# ArduOSD_Simple2222.net
KiCad netlist of a schematic drawn in EAGLE
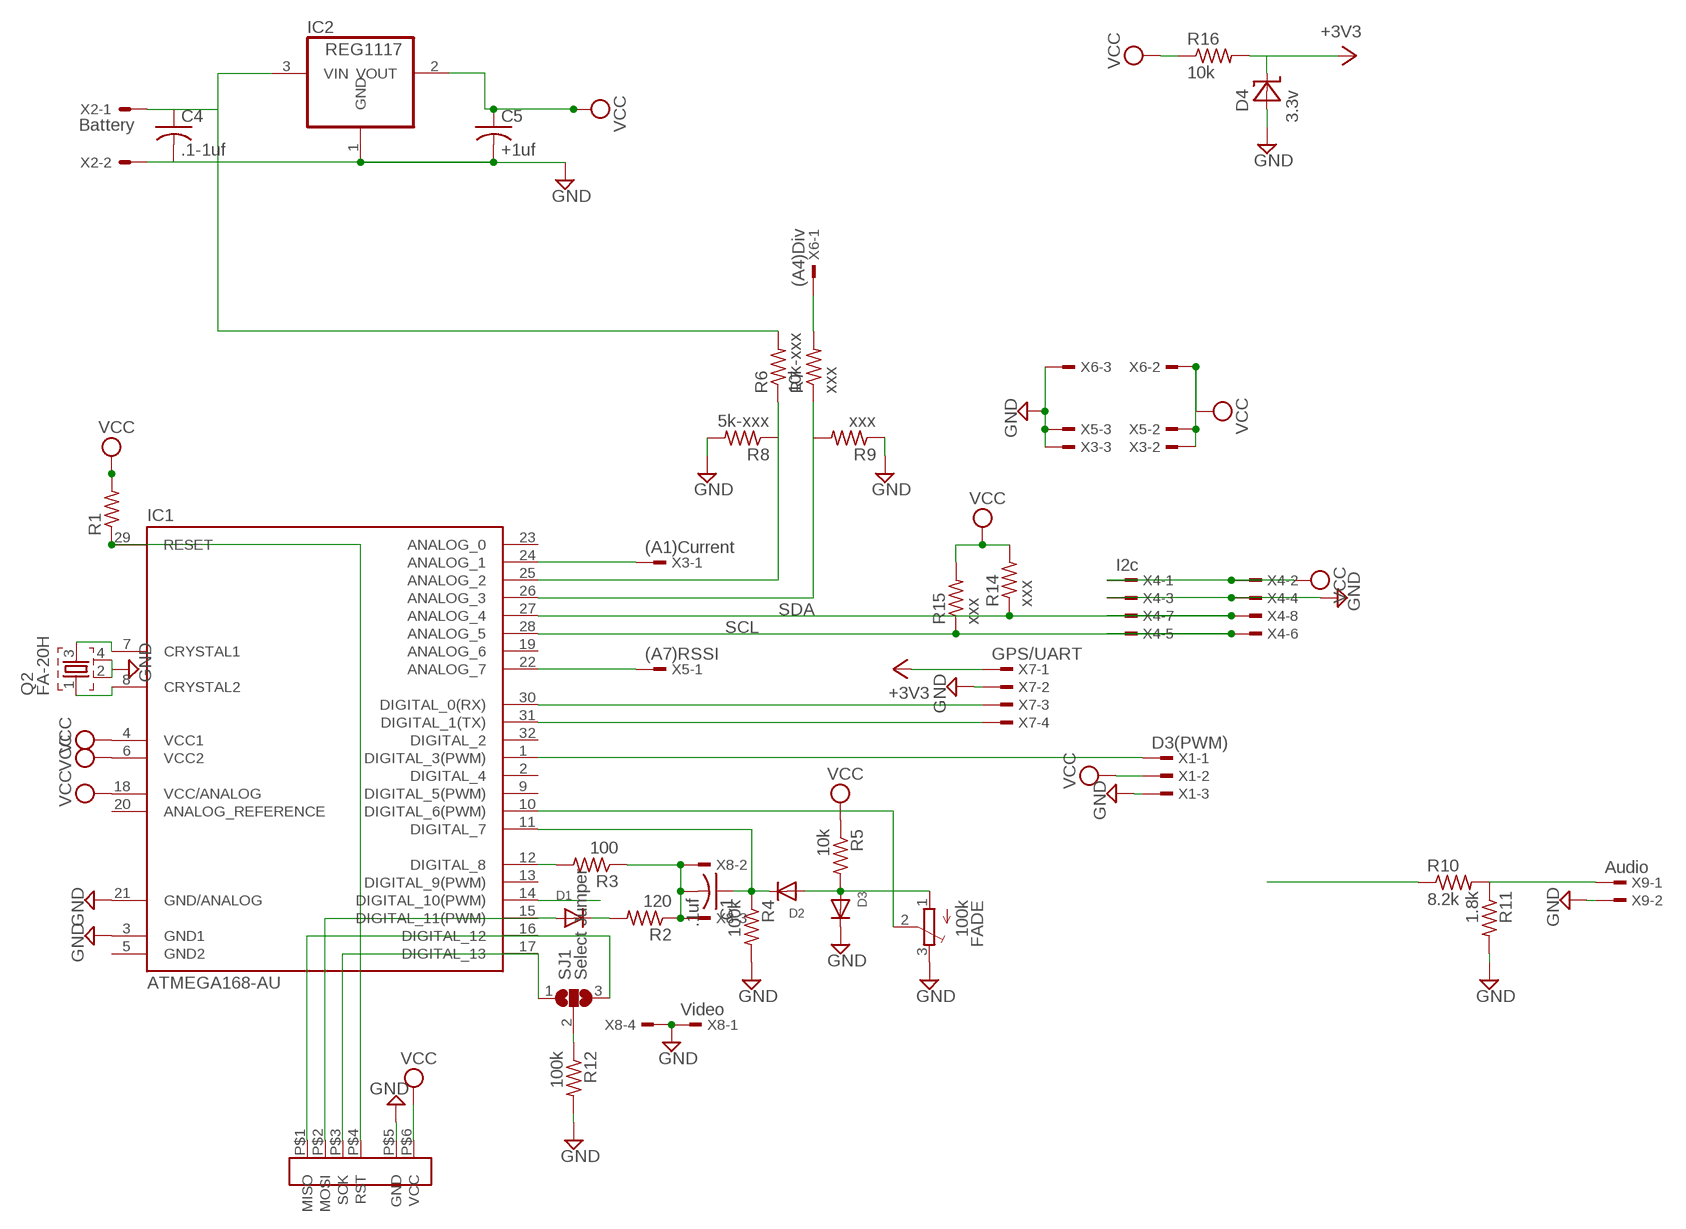
[diagram p0: schematic, sheet 1]

(export (version "E")
  (design (tool "Eeschema 10.0.6"))
  (components
    (comp (ref "C1")
      (value ".1uf")
      (footprint "eagle-import:C0805K")
      (libsource (lib "eagle-import") (part "C-USC0805K"))
    )
    (comp (ref "C4")
      (value ".1-1uf")
      (footprint "eagle-import:C0805K")
      (libsource (lib "eagle-import") (part "C-USC0805K"))
    )
    (comp (ref "C5")
      (value "+1uf")
      (footprint "eagle-import:C0805K")
      (libsource (lib "eagle-import") (part "C-USC0805K"))
    )
    (comp (ref "D1")
      (value "DIODESOT23_WAVE")
      (footprint "eagle-import:SOT23-W")
      (libsource (lib "eagle-import") (part "DIODESOT23_WAVE"))
    )
    (comp (ref "D2")
      (value "DIODESOT23_WAVE")
      (footprint "eagle-import:SOT23-W")
      (libsource (lib "eagle-import") (part "DIODESOT23_WAVE"))
    )
    (comp (ref "D3")
      (value "DIODESOT23_WAVE")
      (footprint "eagle-import:SOT23-W")
      (libsource (lib "eagle-import") (part "DIODESOT23_WAVE"))
    )
    (comp (ref "D4")
      (value "3.3v")
      (footprint "eagle-import:SOD-123")
      (libsource (lib "eagle-import") (part "ZENER_SOD123"))
    )
    (comp (ref "FADE")
      (value "100k")
      (footprint "eagle-import:TC33X")
      (libsource (lib "eagle-import") (part "TRIMPOTTC33X"))
    )
    (comp (ref "IC1")
      (value "ATMEGA168-AU")
      (footprint "eagle-import:TQFP32-08")
      (libsource (lib "eagle-import") (part "ATMEGA168-AU"))
    )
    (comp (ref "IC2")
      (value "REG1117")
      (footprint "eagle-import:SOT223")
      (libsource (lib "eagle-import") (part "REG1117"))
    )
    (comp (ref "Q2")
      (value "FA-20H")
      (footprint "eagle-import:FA-20H")
      (libsource (lib "eagle-import") (part "FA-20H"))
    )
    (comp (ref "R1")
      (value "R-US_R0805")
      (footprint "eagle-import:R0805")
      (libsource (lib "eagle-import") (part "R-US_R0805"))
    )
    (comp (ref "R2")
      (value "120")
      (footprint "eagle-import:R0805")
      (libsource (lib "eagle-import") (part "R-US_R0805"))
    )
    (comp (ref "R3")
      (value "100")
      (footprint "eagle-import:R0805")
      (libsource (lib "eagle-import") (part "R-US_R0805"))
    )
    (comp (ref "R4")
      (value "100k")
      (footprint "eagle-import:R0805")
      (libsource (lib "eagle-import") (part "R-US_R0805"))
    )
    (comp (ref "R5")
      (value "10k")
      (footprint "eagle-import:R0805")
      (libsource (lib "eagle-import") (part "R-US_R0805"))
    )
    (comp (ref "R6")
      (value "10k-xxx")
      (footprint "eagle-import:R0805")
      (libsource (lib "eagle-import") (part "R-US_R0805"))
    )
    (comp (ref "R7")
      (value "xxx")
      (footprint "eagle-import:R0805")
      (libsource (lib "eagle-import") (part "R-US_R0805"))
    )
    (comp (ref "R8")
      (value "5k-xxx")
      (footprint "eagle-import:R0805")
      (libsource (lib "eagle-import") (part "R-US_R0805"))
    )
    (comp (ref "R9")
      (value "xxx")
      (footprint "eagle-import:R0805")
      (libsource (lib "eagle-import") (part "R-US_R0805"))
    )
    (comp (ref "R10")
      (value "8.2k")
      (footprint "eagle-import:R0805")
      (libsource (lib "eagle-import") (part "R-US_R0805"))
    )
    (comp (ref "R11")
      (value "1.8k")
      (footprint "eagle-import:R0805")
      (libsource (lib "eagle-import") (part "R-US_R0805"))
    )
    (comp (ref "R12")
      (value "100k")
      (footprint "eagle-import:R0805")
      (libsource (lib "eagle-import") (part "R-US_R0805"))
    )
    (comp (ref "R14")
      (value "xxx")
      (footprint "eagle-import:R0805")
      (libsource (lib "eagle-import") (part "R-US_R0805"))
    )
    (comp (ref "R15")
      (value "xxx")
      (footprint "eagle-import:R0805")
      (libsource (lib "eagle-import") (part "R-US_R0805"))
    )
    (comp (ref "R16")
      (value "10k")
      (footprint "eagle-import:R0805")
      (libsource (lib "eagle-import") (part "R-US_R0805"))
    )
    (comp (ref "SJ1")
      (value "Select Jumper")
      (footprint "eagle-import:SJ_2")
      (libsource (lib "eagle-import") (part "SJ2W"))
    )
    (comp (ref "U$1")
      (value "LIN_ISP")
      (footprint "eagle-import:LINEAR_ISP")
      (libsource (lib "eagle-import") (part "LIN_ISP"))
    )
    (comp (ref "X1")
      (value "D3(PWM)")
      (footprint "eagle-import:TSW-103-02-S-S")
      (fields (field (name "OC_FARNELL") "unknown") (field (name "OC_NEWARK") "unknown"))
      (libsource (lib "eagle-import") (part "TSW-103-02-S-S"))
    )
    (comp (ref "X2")
      (value "Battery")
      (footprint "eagle-import:22-23-2021")
      (fields (field (name "MF") "MOLEX") (field (name "MPN") "22-23-2021"))
      (libsource (lib "eagle-import") (part "22-23-2021"))
    )
    (comp (ref "X3")
      (value "(A1)Current")
      (footprint "eagle-import:TSW-103-02-S-S")
      (libsource (lib "eagle-import") (part "TSW-103-02-S-S"))
    )
    (comp (ref "X4")
      (value "I2c")
      (footprint "eagle-import:TSW-104-02-S-D-RA")
      (libsource (lib "eagle-import") (part "TSW-104-02-S-D-RA"))
    )
    (comp (ref "X5")
      (value "(A7)RSSI")
      (footprint "eagle-import:TSW-103-02-S-S")
      (libsource (lib "eagle-import") (part "TSW-103-02-S-S"))
    )
    (comp (ref "X6")
      (value "(A4)Div")
      (footprint "eagle-import:TSW-103-02-S-S")
      (fields (field (name "OC_FARNELL") "unknown") (field (name "OC_NEWARK") "unknown"))
      (libsource (lib "eagle-import") (part "TSW-103-02-S-S"))
    )
    (comp (ref "X7")
      (value "GPS/UART")
      (footprint "eagle-import:TSW-104-02-S-S-RA")
      (libsource (lib "eagle-import") (part "TSW-104-02-S-S-RA"))
    )
    (comp (ref "X8")
      (value "Video")
      (footprint "eagle-import:TSW-104-02-S-S-RA")
      (libsource (lib "eagle-import") (part "TSW-104-02-S-S-RA"))
    )
    (comp (ref "X9")
      (value "Audio")
      (footprint "eagle-import:TSW-102-02-S-S-RA")
      (fields (field (name "OC_FARNELL") "unknown") (field (name "OC_NEWARK") "unknown"))
      (libsource (lib "eagle-import") (part "TSW-102-02-S-S-RA"))
    )
  )
  (nets
    (net (code "1") (name "+3V3") (class "Default")
      (node (ref "D4") (pin "1") (pinfunction "C_1") (pintype "passive"))
      (node (ref "R16") (pin "2") (pinfunction "2_2") (pintype "passive"))
      (node (ref "X7") (pin "1") (pinfunction "1_1") (pintype "passive"))
    )
    (net (code "2") (name "/DIGITAL_10") (class "Default")
      (node (ref "IC1") (pin "14") (pinfunction "DIGITAL_10(PWM)_14") (pintype "bidirectional"))
      (node (ref "R10") (pin "1") (pinfunction "1_1") (pintype "passive"))
    )
    (net (code "3") (name "/GND2") (class "Default")
      (node (ref "IC1") (pin "5") (pinfunction "GND2_5") (pintype "power_in"))
    )
    (net (code "4") (name "/SCL") (class "Default")
      (node (ref "IC1") (pin "28") (pinfunction "ANALOG_5_28") (pintype "bidirectional"))
      (node (ref "R15") (pin "1") (pinfunction "1_1") (pintype "passive"))
      (node (ref "X4") (pin "5") (pinfunction "1_5") (pintype "passive"))
      (node (ref "X4") (pin "6") (pinfunction "1_6") (pintype "passive"))
    )
    (net (code "5") (name "/SDA") (class "Default")
      (node (ref "IC1") (pin "27") (pinfunction "ANALOG_4_27") (pintype "bidirectional"))
      (node (ref "R14") (pin "1") (pinfunction "1_1") (pintype "passive"))
      (node (ref "X4") (pin "7") (pinfunction "1_7") (pintype "passive"))
      (node (ref "X4") (pin "8") (pinfunction "1_8") (pintype "passive"))
    )
    (net (code "6") (name "GND") (class "Default")
      (node (ref "C4") (pin "2") (pinfunction "2_2") (pintype "passive"))
      (node (ref "C5") (pin "2") (pinfunction "2_2") (pintype "passive"))
      (node (ref "D3") (pin "3") (pinfunction "C_3") (pintype "passive"))
      (node (ref "D4") (pin "2") (pinfunction "A_2") (pintype "passive"))
      (node (ref "FADE") (pin "3") (pinfunction "E_3") (pintype "passive"))
      (node (ref "IC1") (pin "21") (pinfunction "GND/ANALOG_21") (pintype "power_in"))
      (node (ref "IC1") (pin "3") (pinfunction "GND1_3") (pintype "power_in"))
      (node (ref "IC2") (pin "1") (pinfunction "GND_1") (pintype "power_in"))
      (node (ref "Q2") (pin "2") (pinfunction "2_2") (pintype "passive"))
      (node (ref "Q2") (pin "4") (pinfunction "4_4") (pintype "passive"))
      (node (ref "R11") (pin "2") (pinfunction "2_2") (pintype "passive"))
      (node (ref "R12") (pin "2") (pinfunction "2_2") (pintype "passive"))
      (node (ref "R4") (pin "2") (pinfunction "2_2") (pintype "passive"))
      (node (ref "R8") (pin "2") (pinfunction "2_2") (pintype "passive"))
      (node (ref "R9") (pin "1") (pinfunction "1_1") (pintype "passive"))
      (node (ref "U$1") (pin "P$5") (pinfunction "GND_P$5") (pintype "bidirectional"))
      (node (ref "X1") (pin "3") (pinfunction "1_3") (pintype "passive"))
      (node (ref "X2") (pin "2") (pinfunction "S_2") (pintype "passive"))
      (node (ref "X3") (pin "3") (pinfunction "1_3") (pintype "passive"))
      (node (ref "X4") (pin "3") (pinfunction "1_3") (pintype "passive"))
      (node (ref "X4") (pin "4") (pinfunction "1_4") (pintype "passive"))
      (node (ref "X5") (pin "3") (pinfunction "1_3") (pintype "passive"))
      (node (ref "X6") (pin "3") (pinfunction "1_3") (pintype "passive"))
      (node (ref "X7") (pin "2") (pinfunction "1_2") (pintype "passive"))
      (node (ref "X8") (pin "1") (pinfunction "1_1") (pintype "passive"))
      (node (ref "X8") (pin "4") (pinfunction "1_4") (pintype "passive"))
      (node (ref "X9") (pin "2") (pinfunction "1_2") (pintype "passive"))
    )
    (net (code "7") (name "Net-(D1-A)") (class "Default")
      (node (ref "D1") (pin "1") (pinfunction "A_1") (pintype "passive"))
      (node (ref "IC1") (pin "15") (pinfunction "DIGITAL_11(PWM)_15") (pintype "bidirectional"))
      (node (ref "U$1") (pin "P$2") (pinfunction "MOSI_P$2") (pintype "bidirectional"))
    )
    (net (code "8") (name "Net-(D1-C)") (class "Default")
      (node (ref "D1") (pin "3") (pinfunction "C_3") (pintype "passive"))
      (node (ref "R2") (pin "2") (pinfunction "2_2") (pintype "passive"))
    )
    (net (code "9") (name "Net-(D2-A)") (class "Default")
      (node (ref "D2") (pin "1") (pinfunction "A_1") (pintype "passive"))
      (node (ref "D3") (pin "1") (pinfunction "A_1") (pintype "passive"))
      (node (ref "FADE") (pin "1") (pinfunction "A_1") (pintype "passive"))
      (node (ref "R5") (pin "2") (pinfunction "2_2") (pintype "passive"))
    )
    (net (code "10") (name "Net-(D2-C)") (class "Default")
      (node (ref "C1") (pin "1") (pinfunction "1_1") (pintype "passive"))
      (node (ref "D2") (pin "3") (pinfunction "C_3") (pintype "passive"))
      (node (ref "IC1") (pin "11") (pinfunction "DIGITAL_7_11") (pintype "bidirectional"))
      (node (ref "R4") (pin "1") (pinfunction "1_1") (pintype "passive"))
    )
    (net (code "11") (name "Net-(FADE-S)") (class "Default")
      (node (ref "FADE") (pin "2") (pinfunction "S_2") (pintype "passive"))
      (node (ref "IC1") (pin "10") (pinfunction "DIGITAL_6(PWM)_10") (pintype "bidirectional"))
    )
    (net (code "12") (name "Net-(IC1-ANALOG_1)") (class "Default")
      (node (ref "IC1") (pin "24") (pinfunction "ANALOG_1_24") (pintype "bidirectional"))
      (node (ref "X3") (pin "1") (pinfunction "1_1") (pintype "passive"))
    )
    (net (code "13") (name "Net-(IC1-ANALOG_2)") (class "Default")
      (node (ref "IC1") (pin "25") (pinfunction "ANALOG_2_25") (pintype "bidirectional"))
      (node (ref "R6") (pin "1") (pinfunction "1_1") (pintype "passive"))
      (node (ref "R8") (pin "1") (pinfunction "1_1") (pintype "passive"))
    )
    (net (code "14") (name "Net-(IC1-ANALOG_3)") (class "Default")
      (node (ref "IC1") (pin "26") (pinfunction "ANALOG_3_26") (pintype "bidirectional"))
      (node (ref "R7") (pin "1") (pinfunction "1_1") (pintype "passive"))
      (node (ref "R9") (pin "2") (pinfunction "2_2") (pintype "passive"))
    )
    (net (code "15") (name "Net-(IC1-ANALOG_7)") (class "Default")
      (node (ref "IC1") (pin "22") (pinfunction "ANALOG_7_22") (pintype "passive"))
      (node (ref "X5") (pin "1") (pinfunction "1_1") (pintype "passive"))
    )
    (net (code "16") (name "Net-(IC1-CRYSTAL1)") (class "Default")
      (node (ref "IC1") (pin "7") (pinfunction "CRYSTAL1_7") (pintype "bidirectional"))
      (node (ref "Q2") (pin "3") (pinfunction "3_3") (pintype "passive"))
    )
    (net (code "17") (name "Net-(IC1-CRYSTAL2)") (class "Default")
      (node (ref "IC1") (pin "8") (pinfunction "CRYSTAL2_8") (pintype "bidirectional"))
      (node (ref "Q2") (pin "1") (pinfunction "1_1") (pintype "passive"))
    )
    (net (code "18") (name "Net-(IC1-DIGITAL_0(RX))") (class "Default")
      (node (ref "IC1") (pin "30") (pinfunction "DIGITAL_0(RX)_30") (pintype "bidirectional"))
      (node (ref "X7") (pin "3") (pinfunction "1_3") (pintype "passive"))
    )
    (net (code "19") (name "Net-(IC1-DIGITAL_1(TX))") (class "Default")
      (node (ref "IC1") (pin "31") (pinfunction "DIGITAL_1(TX)_31") (pintype "bidirectional"))
      (node (ref "X7") (pin "4") (pinfunction "1_4") (pintype "passive"))
    )
    (net (code "20") (name "Net-(IC1-DIGITAL_3(PWM))") (class "Default")
      (node (ref "IC1") (pin "1") (pinfunction "DIGITAL_3(PWM)_1") (pintype "bidirectional"))
      (node (ref "X1") (pin "1") (pinfunction "1_1") (pintype "passive"))
    )
    (net (code "21") (name "Net-(IC1-DIGITAL_8)") (class "Default")
      (node (ref "IC1") (pin "12") (pinfunction "DIGITAL_8_12") (pintype "bidirectional"))
      (node (ref "R3") (pin "2") (pinfunction "2_2") (pintype "passive"))
    )
    (net (code "22") (name "Net-(IC1-DIGITAL_12)") (class "Default")
      (node (ref "IC1") (pin "16") (pinfunction "DIGITAL_12_16") (pintype "bidirectional"))
      (node (ref "SJ1") (pin "3") (pinfunction "3_3") (pintype "passive"))
      (node (ref "U$1") (pin "P$1") (pinfunction "MISO_P$1") (pintype "bidirectional"))
    )
    (net (code "23") (name "Net-(IC1-DIGITAL_13)") (class "Default")
      (node (ref "IC1") (pin "17") (pinfunction "DIGITAL_13_17") (pintype "bidirectional"))
      (node (ref "SJ1") (pin "1") (pinfunction "1_1") (pintype "passive"))
      (node (ref "U$1") (pin "P$3") (pinfunction "SCK_P$3") (pintype "bidirectional"))
    )
    (net (code "24") (name "Net-(IC1-RESET)") (class "Default")
      (node (ref "IC1") (pin "29") (pinfunction "RESET_29") (pintype "bidirectional"))
      (node (ref "R1") (pin "1") (pinfunction "1_1") (pintype "passive"))
      (node (ref "U$1") (pin "P$4") (pinfunction "RST_P$4") (pintype "bidirectional"))
    )
    (net (code "25") (name "Net-(IC2-VIN)") (class "Default")
      (node (ref "C4") (pin "1") (pinfunction "1_1") (pintype "passive"))
      (node (ref "IC2") (pin "3") (pinfunction "VIN_3") (pintype "input"))
      (node (ref "R6") (pin "2") (pinfunction "2_2") (pintype "passive"))
      (node (ref "X2") (pin "1") (pinfunction "S_1") (pintype "passive"))
    )
    (net (code "26") (name "Net-(R7-Pad2)") (class "Default")
      (node (ref "R7") (pin "2") (pinfunction "2_2") (pintype "passive"))
      (node (ref "X6") (pin "1") (pinfunction "1_1") (pintype "passive"))
    )
    (net (code "27") (name "Net-(R10-Pad2)") (class "Default")
      (node (ref "R10") (pin "2") (pinfunction "2_2") (pintype "passive"))
      (node (ref "R11") (pin "1") (pinfunction "1_1") (pintype "passive"))
      (node (ref "X9") (pin "1") (pinfunction "1_1") (pintype "passive"))
    )
    (net (code "28") (name "Net-(R12-Pad1)") (class "Default")
      (node (ref "R12") (pin "1") (pinfunction "1_1") (pintype "passive"))
      (node (ref "SJ1") (pin "2") (pinfunction "2_2") (pintype "passive"))
    )
    (net (code "29") (name "Net-(X8B-1)") (class "Default")
      (node (ref "C1") (pin "2") (pinfunction "2_2") (pintype "passive"))
      (node (ref "R2") (pin "1") (pinfunction "1_1") (pintype "passive"))
      (node (ref "R3") (pin "1") (pinfunction "1_1") (pintype "passive"))
      (node (ref "X8") (pin "2") (pinfunction "1_2") (pintype "passive"))
      (node (ref "X8") (pin "3") (pinfunction "1_3") (pintype "passive"))
    )
    (net (code "30") (name "VCC") (class "Default")
      (node (ref "C5") (pin "1") (pinfunction "1_1") (pintype "passive"))
      (node (ref "IC1") (pin "18") (pinfunction "VCC/ANALOG_18") (pintype "passive"))
      (node (ref "IC1") (pin "4") (pinfunction "VCC1_4") (pintype "power_in"))
      (node (ref "IC1") (pin "6") (pinfunction "VCC2_6") (pintype "power_in"))
      (node (ref "IC2") (pin "2") (pinfunction "VOUT_2") (pintype "output"))
      (node (ref "R1") (pin "2") (pinfunction "2_2") (pintype "passive"))
      (node (ref "R14") (pin "2") (pinfunction "2_2") (pintype "passive"))
      (node (ref "R15") (pin "2") (pinfunction "2_2") (pintype "passive"))
      (node (ref "R16") (pin "1") (pinfunction "1_1") (pintype "passive"))
      (node (ref "R5") (pin "1") (pinfunction "1_1") (pintype "passive"))
      (node (ref "U$1") (pin "P$6") (pinfunction "VCC_P$6") (pintype "bidirectional"))
      (node (ref "X1") (pin "2") (pinfunction "1_2") (pintype "passive"))
      (node (ref "X3") (pin "2") (pinfunction "1_2") (pintype "passive"))
      (node (ref "X4") (pin "1") (pinfunction "1_1") (pintype "passive"))
      (node (ref "X4") (pin "2") (pinfunction "1_2") (pintype "passive"))
      (node (ref "X5") (pin "2") (pinfunction "1_2") (pintype "passive"))
      (node (ref "X6") (pin "2") (pinfunction "1_2") (pintype "passive"))
    )
    (net (code "31") (name "unconnected-(IC1-ANALOG_0-Pad23)") (class "Default")
      (node (ref "IC1") (pin "23") (pinfunction "ANALOG_0_23") (pintype "bidirectional"))
    )
    (net (code "32") (name "unconnected-(IC1-ANALOG_6-Pad19)") (class "Default")
      (node (ref "IC1") (pin "19") (pinfunction "ANALOG_6_19") (pintype "passive"))
    )
    (net (code "33") (name "unconnected-(IC1-ANALOG_REFERENCE-Pad20)") (class "Default")
      (node (ref "IC1") (pin "20") (pinfunction "ANALOG_REFERENCE_20") (pintype "passive"))
    )
    (net (code "34") (name "unconnected-(IC1-DIGITAL_2-Pad32)") (class "Default")
      (node (ref "IC1") (pin "32") (pinfunction "DIGITAL_2_32") (pintype "bidirectional"))
    )
    (net (code "35") (name "unconnected-(IC1-DIGITAL_4-Pad2)") (class "Default")
      (node (ref "IC1") (pin "2") (pinfunction "DIGITAL_4_2") (pintype "bidirectional"))
    )
    (net (code "36") (name "unconnected-(IC1-DIGITAL_5(PWM)-Pad9)") (class "Default")
      (node (ref "IC1") (pin "9") (pinfunction "DIGITAL_5(PWM)_9") (pintype "bidirectional"))
    )
    (net (code "37") (name "unconnected-(IC1-DIGITAL_9(PWM)-Pad13)") (class "Default")
      (node (ref "IC1") (pin "13") (pinfunction "DIGITAL_9(PWM)_13") (pintype "bidirectional"))
    )
  )
)
